# junction_cross.net
KiCad netlist of a schematic drawn in Altium Designer
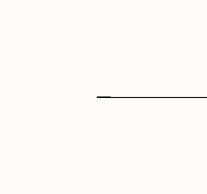
[diagram p0: junction_cross.SchDoc, top left]
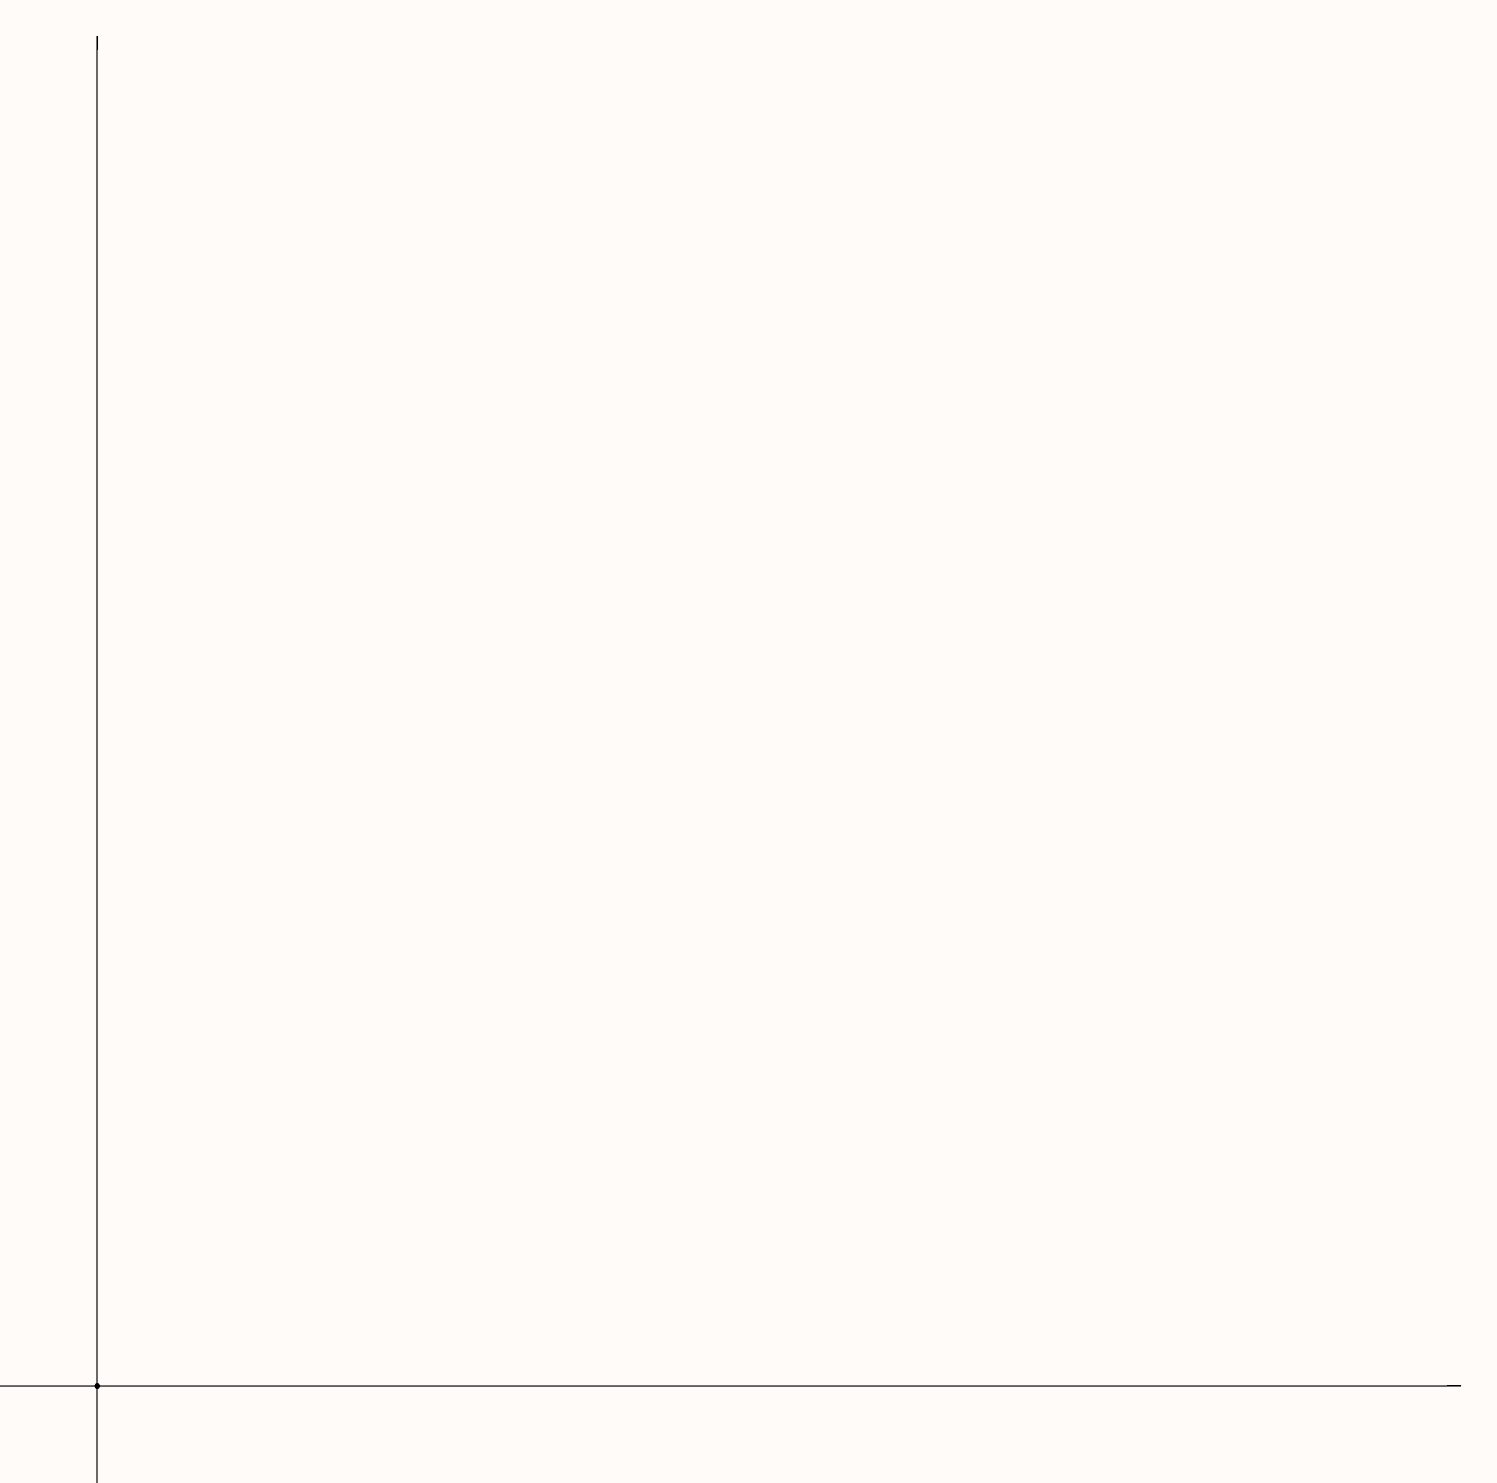
[diagram p1: junction_cross.SchDoc, top right]
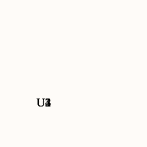
[diagram p2: junction_cross.SchDoc, bottom left]
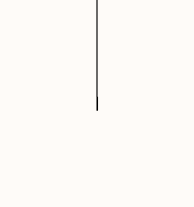
[diagram p3: junction_cross.SchDoc, bottom right]

(export (version "E")
  (design (tool "Eeschema 10.0.6"))
  (components
    (comp (ref "U1") (value "~") (libsource (lib "") (part "root_0_DEVICE__1")))
    (comp (ref "U2") (value "~") (libsource (lib "") (part "root_0_DEVICE__3")))
    (comp (ref "U3") (value "~") (libsource (lib "") (part "root_0_DEVICE__2")))
    (comp (ref "U4") (value "~") (libsource (lib "altium-import") (part "root_0_DEVICE_")))
  )
  (nets
    (net (code "1") (name "Net-(U1-A)") (class "Default")
      (node (ref "U1") (pin "1") (pinfunction "A_1") (pintype "passive"))
      (node (ref "U2") (pin "1") (pinfunction "B_1") (pintype "passive"))
      (node (ref "U3") (pin "1") (pinfunction "C_1") (pintype "passive"))
      (node (ref "U4") (pin "1") (pinfunction "D_1") (pintype "passive"))
    )
  )
)
